# RFID_Controller.net
KiCad netlist of a schematic drawn in EAGLE
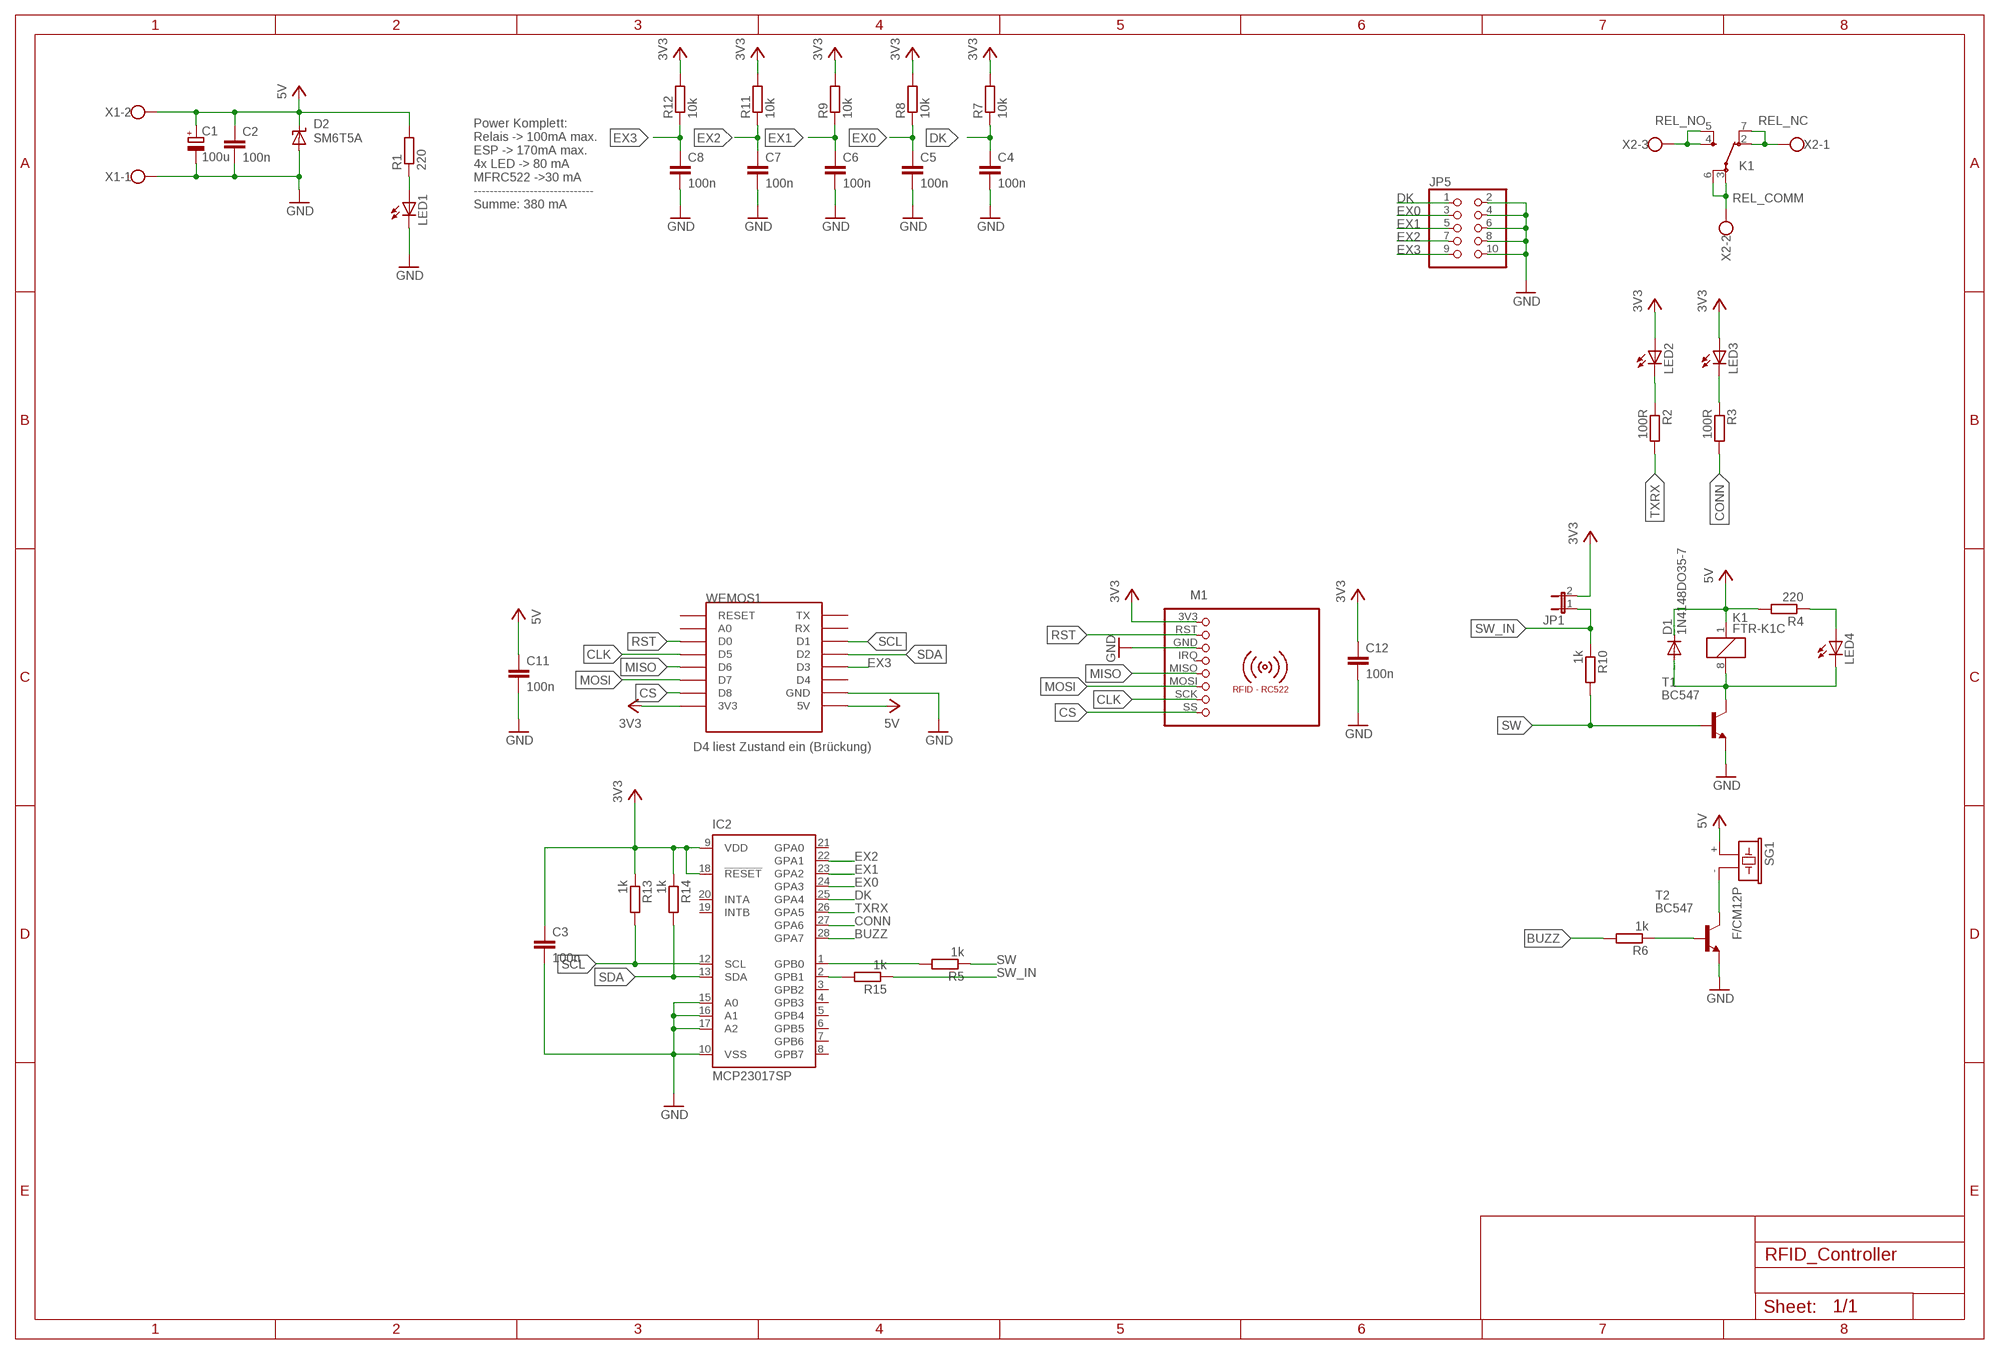
[diagram p0: schematic, sheet 1]

(export (version "E")
  (design (tool "Eeschema 10.0.6"))
  (components
    (comp (ref "C1")
      (value "100u")
      (footprint "eagle-import:E2,5-7")
      (libsource (lib "eagle-import") (part "CPOL-EUE2.5-7"))
    )
    (comp (ref "C2")
      (value "100n")
      (footprint "eagle-import:C050-025X075")
      (libsource (lib "eagle-import") (part "C-EU050-025X075"))
    )
    (comp (ref "C3")
      (value "100n")
      (footprint "eagle-import:C050-025X075")
      (libsource (lib "eagle-import") (part "C-EU050-025X075"))
    )
    (comp (ref "C4")
      (value "100n")
      (footprint "eagle-import:C050-025X075")
      (libsource (lib "eagle-import") (part "C-EU050-025X075"))
    )
    (comp (ref "C5")
      (value "100n")
      (footprint "eagle-import:C050-025X075")
      (libsource (lib "eagle-import") (part "C-EU050-025X075"))
    )
    (comp (ref "C6")
      (value "100n")
      (footprint "eagle-import:C050-025X075")
      (libsource (lib "eagle-import") (part "C-EU050-025X075"))
    )
    (comp (ref "C7")
      (value "100n")
      (footprint "eagle-import:C050-025X075")
      (libsource (lib "eagle-import") (part "C-EU050-025X075"))
    )
    (comp (ref "C8")
      (value "100n")
      (footprint "eagle-import:C050-025X075")
      (libsource (lib "eagle-import") (part "C-EU050-025X075"))
    )
    (comp (ref "C11")
      (value "100n")
      (footprint "eagle-import:C050-025X075")
      (libsource (lib "eagle-import") (part "C-EU050-025X075"))
    )
    (comp (ref "C12")
      (value "100n")
      (footprint "eagle-import:C050-025X075")
      (libsource (lib "eagle-import") (part "C-EU050-025X075"))
    )
    (comp (ref "D1")
      (value "1N4148DO35-7")
      (footprint "eagle-import:DO35-7")
      (libsource (lib "eagle-import") (part "1N4148DO35-7"))
    )
    (comp (ref "D2")
      (value "SM6T5A")
      (footprint "eagle-import:SMBJ")
      (libsource (lib "eagle-import") (part "SUPPRESSOR-SMBJ"))
    )
    (comp (ref "IC2")
      (value "MCP23017SP")
      (footprint "eagle-import:DIL28-3")
      (fields (field (name "MF") "MICROCHIP") (field (name "MPN") "MCP23017-E/SP"))
      (libsource (lib "eagle-import") (part "MCP23017SP"))
    )
    (comp (ref "JP1")
      (value "JP1E")
      (footprint "eagle-import:JP1")
      (libsource (lib "eagle-import") (part "JP1E"))
    )
    (comp (ref "JP5")
      (value "PINHD-2X5")
      (footprint "eagle-import:2X05")
      (libsource (lib "eagle-import") (part "PINHD-2X5"))
    )
    (comp (ref "K1")
      (value "FTR-K1C")
      (footprint "eagle-import:FTR-K1C")
      (libsource (lib "eagle-import") (part "FTR-K1C"))
    )
    (comp (ref "LED1")
      (value "LED3MM")
      (footprint "eagle-import:LED3MM")
      (libsource (lib "eagle-import") (part "LED3MM"))
    )
    (comp (ref "LED2")
      (value "LED3MM")
      (footprint "eagle-import:LED3MM")
      (libsource (lib "eagle-import") (part "LED3MM"))
    )
    (comp (ref "LED3")
      (value "LED3MM")
      (footprint "eagle-import:LED3MM")
      (libsource (lib "eagle-import") (part "LED3MM"))
    )
    (comp (ref "LED4")
      (value "LED3MM")
      (footprint "eagle-import:LED3MM")
      (libsource (lib "eagle-import") (part "LED3MM"))
    )
    (comp (ref "M1")
      (value "RFID-RC522")
      (footprint "eagle-import:RFID-RC522")
      (libsource (lib "eagle-import") (part "RFID-RC522"))
    )
    (comp (ref "R1")
      (value "220")
      (footprint "eagle-import:0204_7")
      (libsource (lib "eagle-import") (part "R-EU_0204/7"))
    )
    (comp (ref "R2")
      (value "100R")
      (footprint "eagle-import:0204_7")
      (libsource (lib "eagle-import") (part "R-EU_0204/7"))
    )
    (comp (ref "R3")
      (value "100R")
      (footprint "eagle-import:0204_7")
      (libsource (lib "eagle-import") (part "R-EU_0204/7"))
    )
    (comp (ref "R4")
      (value "220")
      (footprint "eagle-import:0204_7")
      (libsource (lib "eagle-import") (part "R-EU_0204/7"))
    )
    (comp (ref "R5")
      (value "1k")
      (footprint "eagle-import:0204_7")
      (libsource (lib "eagle-import") (part "R-EU_0204/7"))
    )
    (comp (ref "R6")
      (value "1k")
      (footprint "eagle-import:0204_7")
      (libsource (lib "eagle-import") (part "R-EU_0204/7"))
    )
    (comp (ref "R7")
      (value "10k")
      (footprint "eagle-import:0204_7")
      (libsource (lib "eagle-import") (part "R-EU_0204/7"))
    )
    (comp (ref "R8")
      (value "10k")
      (footprint "eagle-import:0204_7")
      (libsource (lib "eagle-import") (part "R-EU_0204/7"))
    )
    (comp (ref "R9")
      (value "10k")
      (footprint "eagle-import:0204_7")
      (libsource (lib "eagle-import") (part "R-EU_0204/7"))
    )
    (comp (ref "R10")
      (value "1k")
      (footprint "eagle-import:0204_7")
      (libsource (lib "eagle-import") (part "R-EU_0204/7"))
    )
    (comp (ref "R11")
      (value "10k")
      (footprint "eagle-import:0204_7")
      (libsource (lib "eagle-import") (part "R-EU_0204/7"))
    )
    (comp (ref "R12")
      (value "10k")
      (footprint "eagle-import:0204_7")
      (libsource (lib "eagle-import") (part "R-EU_0204/7"))
    )
    (comp (ref "R13")
      (value "1k")
      (footprint "eagle-import:0204_7")
      (libsource (lib "eagle-import") (part "R-EU_0204/7"))
    )
    (comp (ref "R14")
      (value "1k")
      (footprint "eagle-import:0204_7")
      (libsource (lib "eagle-import") (part "R-EU_0204/7"))
    )
    (comp (ref "R15")
      (value "1k")
      (footprint "eagle-import:0204_7")
      (libsource (lib "eagle-import") (part "R-EU_0204/7"))
    )
    (comp (ref "SG1")
      (value "F/CM12P")
      (footprint "eagle-import:F_CM12P")
      (libsource (lib "eagle-import") (part "F/CM12P"))
    )
    (comp (ref "T1")
      (value "BC547")
      (footprint "eagle-import:TO92")
      (libsource (lib "eagle-import") (part "BC547"))
    )
    (comp (ref "T2")
      (value "BC547")
      (footprint "eagle-import:TO92")
      (libsource (lib "eagle-import") (part "BC547"))
    )
    (comp (ref "WEMOS1")
      (value "WEMOS-D1-MINI")
      (footprint "eagle-import:WEMOS-D1-MINI")
      (libsource (lib "eagle-import") (part "WEMOS-D1-MINI"))
    )
    (comp (ref "X1")
      (value "W237-102")
      (footprint "eagle-import:W237-102")
      (fields (field (name "MPN") "237-102"))
      (libsource (lib "eagle-import") (part "W237-102"))
    )
    (comp (ref "X2")
      (value "W237-103")
      (footprint "eagle-import:W237-103")
      (fields (field (name "MPN") "237-103"))
      (libsource (lib "eagle-import") (part "W237-103"))
    )
  )
  (nets
    (net (code "1") (name "/REL_COMM") (class "Default")
      (node (ref "K1") (pin "3") (pinfunction "PA_3") (pintype "passive"))
      (node (ref "K1") (pin "6") (pinfunction "PB_6") (pintype "passive"))
      (node (ref "X2") (pin "2") (pinfunction "KL_2") (pintype "passive"))
    )
    (net (code "2") (name "/REL_NC") (class "Default")
      (node (ref "K1") (pin "2") (pinfunction "OA_2") (pintype "passive"))
      (node (ref "K1") (pin "7") (pinfunction "OB_7") (pintype "passive"))
      (node (ref "X2") (pin "1") (pinfunction "KL_1") (pintype "passive"))
    )
    (net (code "3") (name "/REL_NO") (class "Default")
      (node (ref "K1") (pin "4") (pinfunction "SA_4") (pintype "passive"))
      (node (ref "K1") (pin "5") (pinfunction "SB_5") (pintype "passive"))
      (node (ref "X2") (pin "3") (pinfunction "KL_3") (pintype "passive"))
    )
    (net (code "4") (name "3V3") (class "Default")
      (node (ref "C12") (pin "1") (pinfunction "1_1") (pintype "passive"))
      (node (ref "C3") (pin "1") (pinfunction "1_1") (pintype "passive"))
      (node (ref "IC2") (pin "18") (pinfunction "~{RESET}_18") (pintype "input"))
      (node (ref "IC2") (pin "9") (pinfunction "VDD_9") (pintype "power_in"))
      (node (ref "JP1") (pin "2") (pinfunction "2_2") (pintype "passive"))
      (node (ref "LED2") (pin "A") (pinfunction "A_A") (pintype "passive"))
      (node (ref "LED3") (pin "A") (pinfunction "A_A") (pintype "passive"))
      (node (ref "M1") (pin "3V3") (pinfunction "1_3V3") (pintype "passive"))
      (node (ref "R11") (pin "2") (pinfunction "2_2") (pintype "passive"))
      (node (ref "R12") (pin "2") (pinfunction "2_2") (pintype "passive"))
      (node (ref "R13") (pin "1") (pinfunction "1_1") (pintype "passive"))
      (node (ref "R14") (pin "1") (pinfunction "1_1") (pintype "passive"))
      (node (ref "R7") (pin "2") (pinfunction "2_2") (pintype "passive"))
      (node (ref "R8") (pin "2") (pinfunction "2_2") (pintype "passive"))
      (node (ref "R9") (pin "2") (pinfunction "2_2") (pintype "passive"))
      (node (ref "WEMOS1") (pin "3V3") (pinfunction "3V3_3V3") (pintype "bidirectional"))
    )
    (net (code "5") (name "5V") (class "Default")
      (node (ref "C1") (pin "+") (pinfunction "+_+") (pintype "passive"))
      (node (ref "C11") (pin "1") (pinfunction "1_1") (pintype "passive"))
      (node (ref "C2") (pin "1") (pinfunction "1_1") (pintype "passive"))
      (node (ref "D1") (pin "C") (pinfunction "C_C") (pintype "passive"))
      (node (ref "D2") (pin "C") (pinfunction "C_C") (pintype "passive"))
      (node (ref "K1") (pin "1") (pinfunction "1_1") (pintype "passive"))
      (node (ref "R1") (pin "2") (pinfunction "2_2") (pintype "passive"))
      (node (ref "R4") (pin "2") (pinfunction "2_2") (pintype "passive"))
      (node (ref "SG1") (pin "+") (pinfunction "1_+") (pintype "passive"))
      (node (ref "WEMOS1") (pin "5V") (pinfunction "5V_5V") (pintype "bidirectional"))
      (node (ref "X1") (pin "2") (pinfunction "KL_2") (pintype "passive"))
    )
    (net (code "6") (name "BUZZ") (class "Default")
      (node (ref "IC2") (pin "28") (pinfunction "GPA7_28") (pintype "bidirectional"))
      (node (ref "R6") (pin "2") (pinfunction "2_2") (pintype "passive"))
    )
    (net (code "7") (name "CLK") (class "Default")
      (node (ref "M1") (pin "SCK") (pinfunction "7_SCK") (pintype "passive"))
      (node (ref "WEMOS1") (pin "D5") (pinfunction "D5_D5") (pintype "bidirectional"))
    )
    (net (code "8") (name "CONN") (class "Default")
      (node (ref "IC2") (pin "27") (pinfunction "GPA6_27") (pintype "bidirectional"))
      (node (ref "R3") (pin "2") (pinfunction "2_2") (pintype "passive"))
    )
    (net (code "9") (name "CS") (class "Default")
      (node (ref "M1") (pin "SS") (pinfunction "8_SS") (pintype "passive"))
      (node (ref "WEMOS1") (pin "D8") (pinfunction "D8_D8") (pintype "bidirectional"))
    )
    (net (code "10") (name "DK") (class "Default")
      (node (ref "C4") (pin "1") (pinfunction "1_1") (pintype "passive"))
      (node (ref "IC2") (pin "25") (pinfunction "GPA4_25") (pintype "bidirectional"))
      (node (ref "JP5") (pin "1") (pinfunction "1_1") (pintype "passive"))
      (node (ref "R7") (pin "1") (pinfunction "1_1") (pintype "passive"))
    )
    (net (code "11") (name "EX0") (class "Default")
      (node (ref "C5") (pin "1") (pinfunction "1_1") (pintype "passive"))
      (node (ref "IC2") (pin "24") (pinfunction "GPA3_24") (pintype "bidirectional"))
      (node (ref "JP5") (pin "3") (pinfunction "3_3") (pintype "passive"))
      (node (ref "R8") (pin "1") (pinfunction "1_1") (pintype "passive"))
    )
    (net (code "12") (name "EX1") (class "Default")
      (node (ref "C6") (pin "1") (pinfunction "1_1") (pintype "passive"))
      (node (ref "IC2") (pin "23") (pinfunction "GPA2_23") (pintype "bidirectional"))
      (node (ref "JP5") (pin "5") (pinfunction "5_5") (pintype "passive"))
      (node (ref "R9") (pin "1") (pinfunction "1_1") (pintype "passive"))
    )
    (net (code "13") (name "EX2") (class "Default")
      (node (ref "C7") (pin "1") (pinfunction "1_1") (pintype "passive"))
      (node (ref "IC2") (pin "22") (pinfunction "GPA1_22") (pintype "bidirectional"))
      (node (ref "JP5") (pin "7") (pinfunction "7_7") (pintype "passive"))
      (node (ref "R11") (pin "1") (pinfunction "1_1") (pintype "passive"))
    )
    (net (code "14") (name "EX3") (class "Default")
      (node (ref "C8") (pin "1") (pinfunction "1_1") (pintype "passive"))
      (node (ref "JP5") (pin "9") (pinfunction "9_9") (pintype "passive"))
      (node (ref "R12") (pin "1") (pinfunction "1_1") (pintype "passive"))
      (node (ref "WEMOS1") (pin "D3") (pinfunction "D3_D3") (pintype "bidirectional"))
    )
    (net (code "15") (name "GND") (class "Default")
      (node (ref "C1") (pin "-") (pinfunction "-_-") (pintype "passive"))
      (node (ref "C11") (pin "2") (pinfunction "2_2") (pintype "passive"))
      (node (ref "C12") (pin "2") (pinfunction "2_2") (pintype "passive"))
      (node (ref "C2") (pin "2") (pinfunction "2_2") (pintype "passive"))
      (node (ref "C3") (pin "2") (pinfunction "2_2") (pintype "passive"))
      (node (ref "C4") (pin "2") (pinfunction "2_2") (pintype "passive"))
      (node (ref "C5") (pin "2") (pinfunction "2_2") (pintype "passive"))
      (node (ref "C6") (pin "2") (pinfunction "2_2") (pintype "passive"))
      (node (ref "C7") (pin "2") (pinfunction "2_2") (pintype "passive"))
      (node (ref "C8") (pin "2") (pinfunction "2_2") (pintype "passive"))
      (node (ref "D2") (pin "A") (pinfunction "A_A") (pintype "passive"))
      (node (ref "IC2") (pin "10") (pinfunction "VSS_10") (pintype "power_in"))
      (node (ref "IC2") (pin "15") (pinfunction "A0_15") (pintype "input"))
      (node (ref "IC2") (pin "16") (pinfunction "A1_16") (pintype "input"))
      (node (ref "IC2") (pin "17") (pinfunction "A2_17") (pintype "input"))
      (node (ref "JP5") (pin "10") (pinfunction "10_10") (pintype "passive"))
      (node (ref "JP5") (pin "2") (pinfunction "2_2") (pintype "passive"))
      (node (ref "JP5") (pin "4") (pinfunction "4_4") (pintype "passive"))
      (node (ref "JP5") (pin "6") (pinfunction "6_6") (pintype "passive"))
      (node (ref "JP5") (pin "8") (pinfunction "8_8") (pintype "passive"))
      (node (ref "LED1") (pin "K") (pinfunction "C_K") (pintype "passive"))
      (node (ref "M1") (pin "GND") (pinfunction "3_GND") (pintype "passive"))
      (node (ref "T1") (pin "1") (pinfunction "E_1") (pintype "passive"))
      (node (ref "T2") (pin "1") (pinfunction "E_1") (pintype "passive"))
      (node (ref "WEMOS1") (pin "GND") (pinfunction "GND_GND") (pintype "bidirectional"))
      (node (ref "X1") (pin "1") (pinfunction "KL_1") (pintype "passive"))
    )
    (net (code "16") (name "MISO") (class "Default")
      (node (ref "M1") (pin "MISO") (pinfunction "5_MISO") (pintype "passive"))
      (node (ref "WEMOS1") (pin "D6") (pinfunction "D6_D6") (pintype "bidirectional"))
    )
    (net (code "17") (name "MOSI") (class "Default")
      (node (ref "M1") (pin "MOSI") (pinfunction "6_MOSI") (pintype "passive"))
      (node (ref "WEMOS1") (pin "D7") (pinfunction "D7_D7") (pintype "bidirectional"))
    )
    (net (code "18") (name "Net-(IC2-GPB0)") (class "Default")
      (node (ref "IC2") (pin "1") (pinfunction "GPB0_1") (pintype "bidirectional"))
      (node (ref "R5") (pin "2") (pinfunction "2_2") (pintype "passive"))
    )
    (net (code "19") (name "Net-(K1B-2)") (class "Default")
      (node (ref "D1") (pin "A") (pinfunction "A_A") (pintype "passive"))
      (node (ref "K1") (pin "8") (pinfunction "2_8") (pintype "passive"))
      (node (ref "LED4") (pin "K") (pinfunction "C_K") (pintype "passive"))
      (node (ref "T1") (pin "3") (pinfunction "C_3") (pintype "passive"))
    )
    (net (code "20") (name "Net-(LED1-PadA)") (class "Default")
      (node (ref "LED1") (pin "A") (pinfunction "A_A") (pintype "passive"))
      (node (ref "R1") (pin "1") (pinfunction "1_1") (pintype "passive"))
    )
    (net (code "21") (name "Net-(LED2-C)") (class "Default")
      (node (ref "LED2") (pin "K") (pinfunction "C_K") (pintype "passive"))
      (node (ref "R2") (pin "1") (pinfunction "1_1") (pintype "passive"))
    )
    (net (code "22") (name "Net-(LED3-C)") (class "Default")
      (node (ref "LED3") (pin "K") (pinfunction "C_K") (pintype "passive"))
      (node (ref "R3") (pin "1") (pinfunction "1_1") (pintype "passive"))
    )
    (net (code "23") (name "Net-(LED4-PadA)") (class "Default")
      (node (ref "LED4") (pin "A") (pinfunction "A_A") (pintype "passive"))
      (node (ref "R4") (pin "1") (pinfunction "1_1") (pintype "passive"))
    )
    (net (code "24") (name "Net-(SG1-2)") (class "Default")
      (node (ref "SG1") (pin "-") (pinfunction "2_-") (pintype "passive"))
      (node (ref "T2") (pin "3") (pinfunction "C_3") (pintype "passive"))
    )
    (net (code "25") (name "Net-(T2-B)") (class "Default")
      (node (ref "R6") (pin "1") (pinfunction "1_1") (pintype "passive"))
      (node (ref "T2") (pin "2") (pinfunction "B_2") (pintype "passive"))
    )
    (net (code "26") (name "RST") (class "Default")
      (node (ref "M1") (pin "RST") (pinfunction "2_RST") (pintype "passive"))
      (node (ref "WEMOS1") (pin "D0") (pinfunction "D0_D0") (pintype "bidirectional"))
    )
    (net (code "27") (name "SCL") (class "Default")
      (node (ref "IC2") (pin "12") (pinfunction "SCL_12") (pintype "input"))
      (node (ref "R13") (pin "2") (pinfunction "2_2") (pintype "passive"))
      (node (ref "WEMOS1") (pin "D1") (pinfunction "D1_D1") (pintype "bidirectional"))
    )
    (net (code "28") (name "SDA") (class "Default")
      (node (ref "IC2") (pin "13") (pinfunction "SDA_13") (pintype "bidirectional"))
      (node (ref "R14") (pin "2") (pinfunction "2_2") (pintype "passive"))
      (node (ref "WEMOS1") (pin "D2") (pinfunction "D2_D2") (pintype "bidirectional"))
    )
    (net (code "29") (name "SW") (class "Default")
      (node (ref "IC2") (pin "2") (pinfunction "GPB1_2") (pintype "bidirectional"))
      (node (ref "R10") (pin "2") (pinfunction "2_2") (pintype "passive"))
      (node (ref "R15") (pin "2") (pinfunction "2_2") (pintype "passive"))
      (node (ref "R5") (pin "1") (pinfunction "1_1") (pintype "passive"))
      (node (ref "T1") (pin "2") (pinfunction "B_2") (pintype "passive"))
    )
    (net (code "30") (name "SW_IN") (class "Default")
      (node (ref "JP1") (pin "1") (pinfunction "1_1") (pintype "passive"))
      (node (ref "R10") (pin "1") (pinfunction "1_1") (pintype "passive"))
      (node (ref "R15") (pin "1") (pinfunction "1_1") (pintype "passive"))
    )
    (net (code "31") (name "TXRX") (class "Default")
      (node (ref "IC2") (pin "26") (pinfunction "GPA5_26") (pintype "bidirectional"))
      (node (ref "R2") (pin "2") (pinfunction "2_2") (pintype "passive"))
    )
    (net (code "32") (name "unconnected-(IC2-GPA0-Pad21)") (class "Default")
      (node (ref "IC2") (pin "21") (pinfunction "GPA0_21") (pintype "bidirectional"))
    )
    (net (code "33") (name "unconnected-(IC2-GPB2-Pad3)") (class "Default")
      (node (ref "IC2") (pin "3") (pinfunction "GPB2_3") (pintype "bidirectional"))
    )
    (net (code "34") (name "unconnected-(IC2-GPB3-Pad4)") (class "Default")
      (node (ref "IC2") (pin "4") (pinfunction "GPB3_4") (pintype "bidirectional"))
    )
    (net (code "35") (name "unconnected-(IC2-GPB4-Pad5)") (class "Default")
      (node (ref "IC2") (pin "5") (pinfunction "GPB4_5") (pintype "bidirectional"))
    )
    (net (code "36") (name "unconnected-(IC2-GPB5-Pad6)") (class "Default")
      (node (ref "IC2") (pin "6") (pinfunction "GPB5_6") (pintype "bidirectional"))
    )
    (net (code "37") (name "unconnected-(IC2-GPB6-Pad7)") (class "Default")
      (node (ref "IC2") (pin "7") (pinfunction "GPB6_7") (pintype "bidirectional"))
    )
    (net (code "38") (name "unconnected-(IC2-GPB7-Pad8)") (class "Default")
      (node (ref "IC2") (pin "8") (pinfunction "GPB7_8") (pintype "bidirectional"))
    )
    (net (code "39") (name "unconnected-(IC2-INTA-Pad20)") (class "Default")
      (node (ref "IC2") (pin "20") (pinfunction "INTA_20") (pintype "output"))
    )
    (net (code "40") (name "unconnected-(IC2-INTB-Pad19)") (class "Default")
      (node (ref "IC2") (pin "19") (pinfunction "INTB_19") (pintype "output"))
    )
    (net (code "41") (name "unconnected-(M1-4-PadIRQ)") (class "Default")
      (node (ref "M1") (pin "IRQ") (pinfunction "4_IRQ") (pintype "passive"))
    )
    (net (code "42") (name "unconnected-(WEMOS1-PadA0)") (class "Default")
      (node (ref "WEMOS1") (pin "A0") (pinfunction "A0_A0") (pintype "bidirectional"))
    )
    (net (code "43") (name "unconnected-(WEMOS1-PadD4)") (class "Default")
      (node (ref "WEMOS1") (pin "D4") (pinfunction "D4_D4") (pintype "bidirectional"))
    )
    (net (code "44") (name "unconnected-(WEMOS1-PadRESET)") (class "Default")
      (node (ref "WEMOS1") (pin "RESET") (pinfunction "RESET_RESET") (pintype "bidirectional"))
    )
    (net (code "45") (name "unconnected-(WEMOS1-PadRX)") (class "Default")
      (node (ref "WEMOS1") (pin "RX") (pinfunction "RX_RX") (pintype "bidirectional"))
    )
    (net (code "46") (name "unconnected-(WEMOS1-PadTX)") (class "Default")
      (node (ref "WEMOS1") (pin "TX") (pinfunction "TX_TX") (pintype "bidirectional"))
    )
  )
)
